# ASD2116.net
KiCad netlist of a schematic drawn in EAGLE
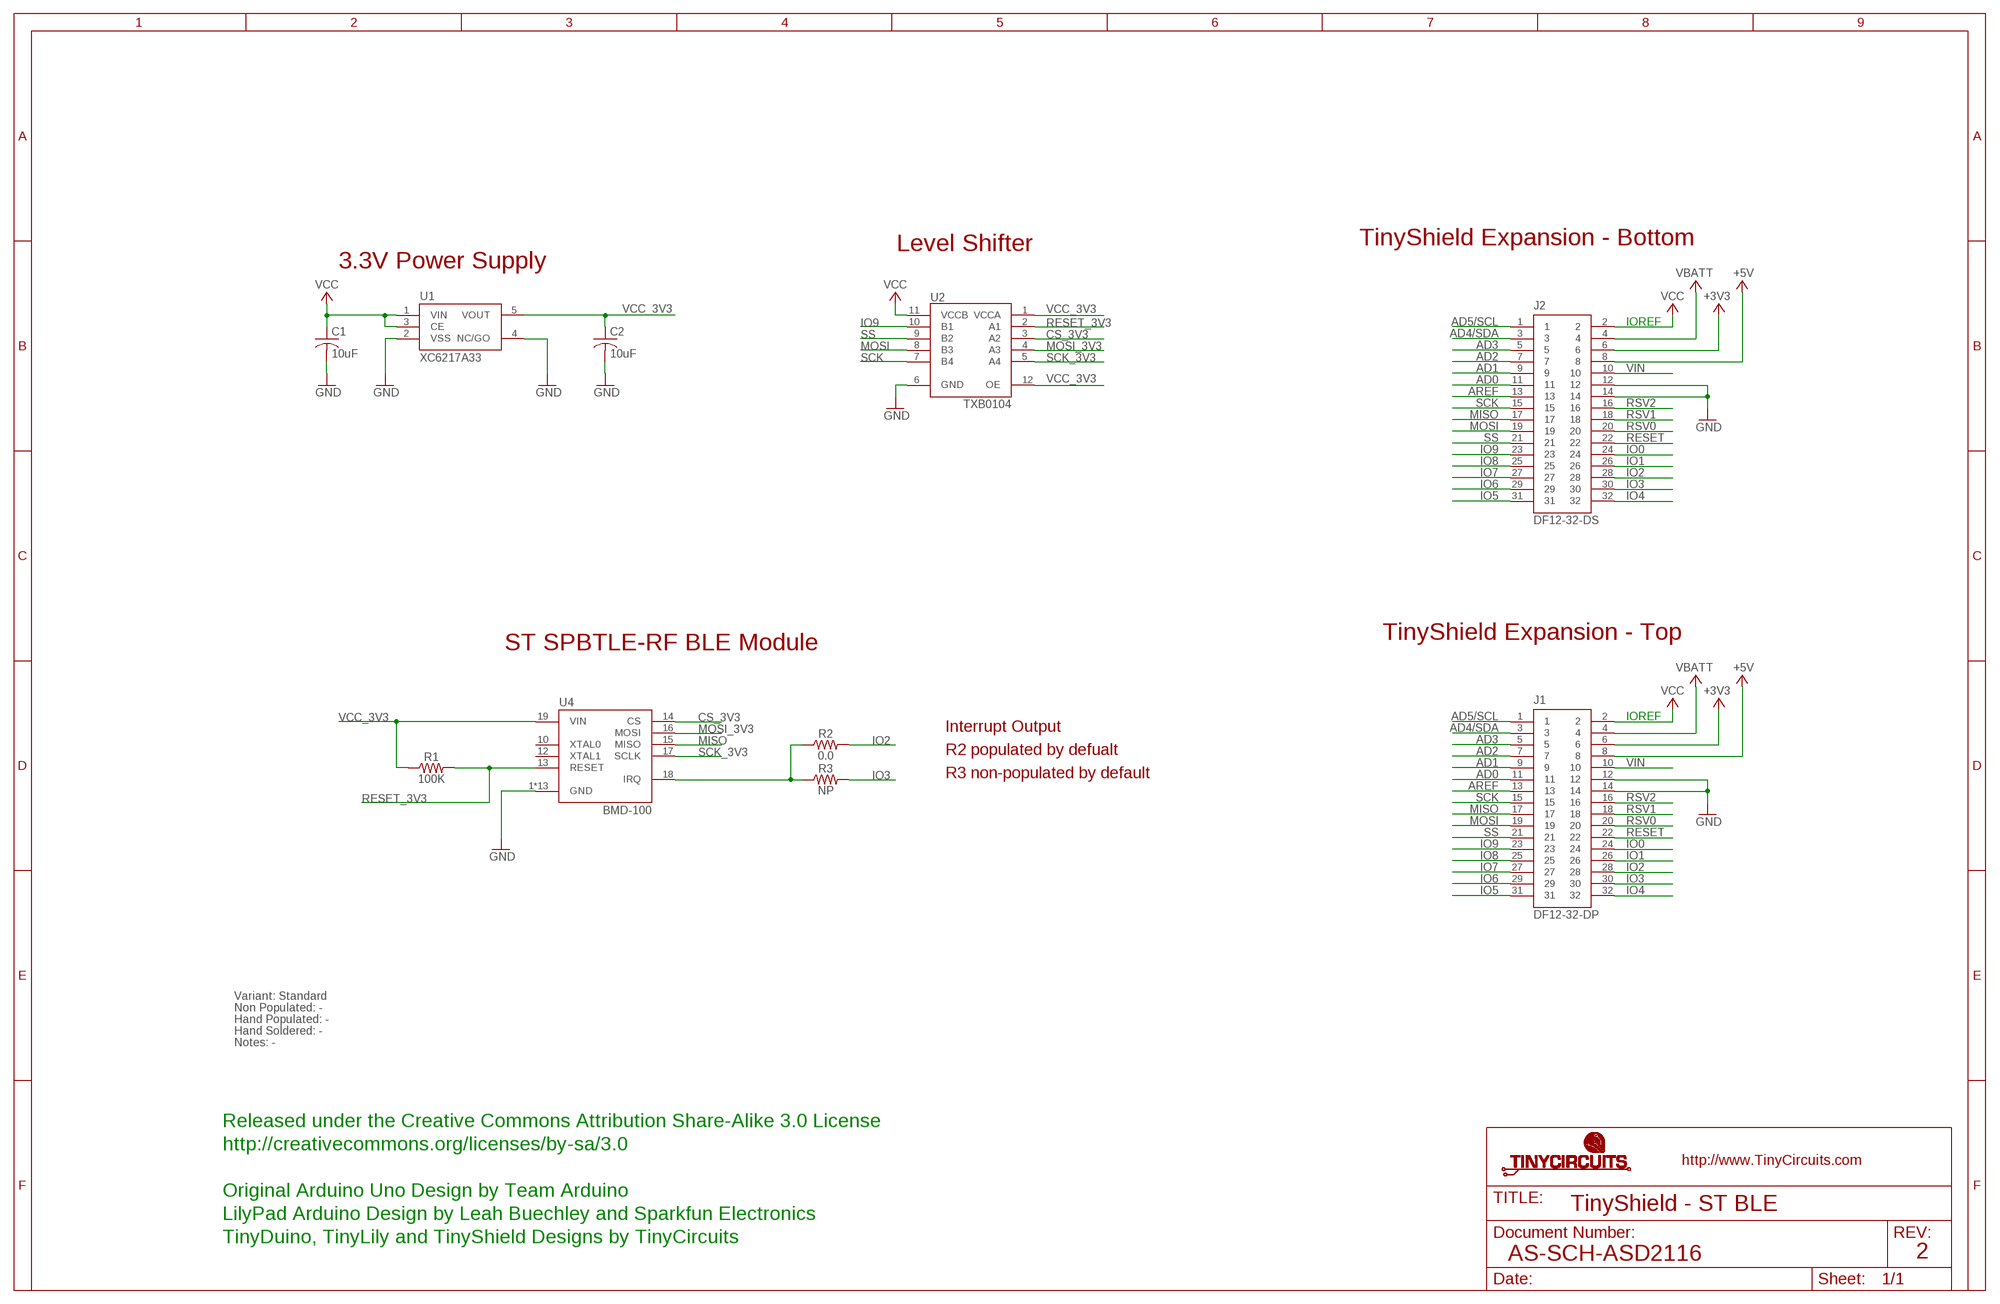
[diagram p0: schematic, sheet 1]

(export (version "E")
  (design (tool "Eeschema 10.0.6"))
  (components
    (comp (ref "C1")
      (value "10uF")
      (footprint "eagle-import:C0603")
      (fields (field (name "PARTNO") "AS-ITM-00002") (field (name "PARTNO_1") "AS-ITM-00002"))
      (libsource (lib "eagle-import") (part "AS-ITM-00002"))
    )
    (comp (ref "C2")
      (value "10uF")
      (footprint "eagle-import:C0603")
      (fields (field (name "PARTNO") "AS-ITM-00002") (field (name "PARTNO_1") "AS-ITM-00002"))
      (libsource (lib "eagle-import") (part "AS-ITM-00002"))
    )
    (comp (ref "J1")
      (value "DF12-32-DP")
      (footprint "eagle-import:DF12-32-DP")
      (fields (field (name "PARTNO") "AS-ITM-00015") (field (name "PARTNO_1") "AS-ITM-00015"))
      (libsource (lib "eagle-import") (part "AS-ITM-00015"))
    )
    (comp (ref "J2")
      (value "DF12-32-DS")
      (footprint "eagle-import:DF12-32-DS")
      (fields (field (name "PARTNO") "AS-ITM-00012") (field (name "PARTNO_1") "AS-ITM-00012"))
      (libsource (lib "eagle-import") (part "AS-ITM-00012"))
    )
    (comp (ref "R1")
      (value "100K")
      (footprint "eagle-import:0402")
      (fields (field (name "PARTNO") "AS-ITM-00004"))
      (libsource (lib "eagle-import") (part "AS-ITM-00004"))
    )
    (comp (ref "R2")
      (value "0.0")
      (footprint "eagle-import:0402")
      (fields (field (name "PARTNO") "AS-ITM-00076") (field (name "PARTNO_1") "AS-ITM-00076"))
      (libsource (lib "eagle-import") (part "AS-ITM-00076"))
    )
    (comp (ref "R3")
      (value "NP")
      (footprint "eagle-import:0402")
      (fields (field (name "PARTNO") "AS-ITM-00076") (field (name "PARTNO_1") "AS-ITM-00076"))
      (libsource (lib "eagle-import") (part "AS-ITM-00076"))
    )
    (comp (ref "U1")
      (value "XC6217A33")
      (footprint "eagle-import:SOT-25")
      (fields (field (name "PARTNO") "AS-ITM-00249") (field (name "PARTNO_1") "AS-ITM-00249"))
      (libsource (lib "eagle-import") (part "AS-ITM-00249"))
    )
    (comp (ref "U2")
      (value "TXB0104")
      (footprint "eagle-import:UQFN-12")
      (fields (field (name "PARTNO") "AS-ITM-00048"))
      (libsource (lib "eagle-import") (part "AS-ITM-00048"))
    )
    (comp (ref "U4")
      (value "BMD-100")
      (footprint "eagle-import:BMD-100")
      (fields (field (name "PARTNO") "AS-ITM-00402"))
      (libsource (lib "eagle-import") (part "AS-ITM-00402"))
    )
  )
  (nets
    (net (code "1") (name "+3V3") (class "Default")
      (node (ref "J1") (pin "6") (pinfunction "6_6") (pintype "bidirectional"))
      (node (ref "J2") (pin "6") (pinfunction "6_6") (pintype "bidirectional"))
    )
    (net (code "2") (name "+5V") (class "Default")
      (node (ref "J1") (pin "8") (pinfunction "8_8") (pintype "bidirectional"))
      (node (ref "J2") (pin "8") (pinfunction "8_8") (pintype "bidirectional"))
    )
    (net (code "3") (name "/AD0") (class "Default")
      (node (ref "J1") (pin "11") (pinfunction "11_11") (pintype "bidirectional"))
      (node (ref "J2") (pin "11") (pinfunction "11_11") (pintype "bidirectional"))
    )
    (net (code "4") (name "/AD1") (class "Default")
      (node (ref "J1") (pin "9") (pinfunction "9_9") (pintype "bidirectional"))
      (node (ref "J2") (pin "9") (pinfunction "9_9") (pintype "bidirectional"))
    )
    (net (code "5") (name "/AD2") (class "Default")
      (node (ref "J1") (pin "7") (pinfunction "7_7") (pintype "bidirectional"))
      (node (ref "J2") (pin "7") (pinfunction "7_7") (pintype "bidirectional"))
    )
    (net (code "6") (name "/AD3") (class "Default")
      (node (ref "J1") (pin "5") (pinfunction "5_5") (pintype "bidirectional"))
      (node (ref "J2") (pin "5") (pinfunction "5_5") (pintype "bidirectional"))
    )
    (net (code "7") (name "/AD4{slash}SDA") (class "Default")
      (node (ref "J1") (pin "3") (pinfunction "3_3") (pintype "bidirectional"))
      (node (ref "J2") (pin "3") (pinfunction "3_3") (pintype "bidirectional"))
    )
    (net (code "8") (name "/AD5{slash}SCL") (class "Default")
      (node (ref "J1") (pin "1") (pinfunction "1_1") (pintype "bidirectional"))
      (node (ref "J2") (pin "1") (pinfunction "1_1") (pintype "bidirectional"))
    )
    (net (code "9") (name "/AREF") (class "Default")
      (node (ref "J1") (pin "13") (pinfunction "13_13") (pintype "bidirectional"))
      (node (ref "J2") (pin "13") (pinfunction "13_13") (pintype "bidirectional"))
    )
    (net (code "10") (name "/CS_3V3") (class "Default")
      (node (ref "U2") (pin "3") (pinfunction "A2_3") (pintype "bidirectional"))
      (node (ref "U4") (pin "14") (pinfunction "CS_14") (pintype "bidirectional"))
    )
    (net (code "11") (name "/IO0") (class "Default")
      (node (ref "J1") (pin "24") (pinfunction "24_24") (pintype "bidirectional"))
      (node (ref "J2") (pin "24") (pinfunction "24_24") (pintype "bidirectional"))
    )
    (net (code "12") (name "/IO1") (class "Default")
      (node (ref "J1") (pin "26") (pinfunction "26_26") (pintype "bidirectional"))
      (node (ref "J2") (pin "26") (pinfunction "26_26") (pintype "bidirectional"))
    )
    (net (code "13") (name "/IO2") (class "Default")
      (node (ref "J1") (pin "28") (pinfunction "28_28") (pintype "bidirectional"))
      (node (ref "J2") (pin "28") (pinfunction "28_28") (pintype "bidirectional"))
      (node (ref "R2") (pin "2") (pinfunction "2_2") (pintype "passive"))
    )
    (net (code "14") (name "/IO3") (class "Default")
      (node (ref "J1") (pin "30") (pinfunction "30_30") (pintype "bidirectional"))
      (node (ref "J2") (pin "30") (pinfunction "30_30") (pintype "bidirectional"))
      (node (ref "R3") (pin "2") (pinfunction "2_2") (pintype "passive"))
    )
    (net (code "15") (name "/IO4") (class "Default")
      (node (ref "J1") (pin "32") (pinfunction "32_32") (pintype "bidirectional"))
      (node (ref "J2") (pin "32") (pinfunction "32_32") (pintype "bidirectional"))
    )
    (net (code "16") (name "/IO5") (class "Default")
      (node (ref "J1") (pin "31") (pinfunction "31_31") (pintype "bidirectional"))
      (node (ref "J2") (pin "31") (pinfunction "31_31") (pintype "bidirectional"))
    )
    (net (code "17") (name "/IO6") (class "Default")
      (node (ref "J1") (pin "29") (pinfunction "29_29") (pintype "bidirectional"))
      (node (ref "J2") (pin "29") (pinfunction "29_29") (pintype "bidirectional"))
    )
    (net (code "18") (name "/IO7") (class "Default")
      (node (ref "J1") (pin "27") (pinfunction "27_27") (pintype "bidirectional"))
      (node (ref "J2") (pin "27") (pinfunction "27_27") (pintype "bidirectional"))
    )
    (net (code "19") (name "/IO8") (class "Default")
      (node (ref "J1") (pin "25") (pinfunction "25_25") (pintype "bidirectional"))
      (node (ref "J2") (pin "25") (pinfunction "25_25") (pintype "bidirectional"))
    )
    (net (code "20") (name "/IO9") (class "Default")
      (node (ref "J1") (pin "23") (pinfunction "23_23") (pintype "bidirectional"))
      (node (ref "J2") (pin "23") (pinfunction "23_23") (pintype "bidirectional"))
      (node (ref "U2") (pin "10") (pinfunction "B1_10") (pintype "bidirectional"))
    )
    (net (code "21") (name "/MISO") (class "Default")
      (node (ref "J1") (pin "17") (pinfunction "17_17") (pintype "bidirectional"))
      (node (ref "J2") (pin "17") (pinfunction "17_17") (pintype "bidirectional"))
      (node (ref "U4") (pin "15") (pinfunction "MISO_15") (pintype "bidirectional"))
    )
    (net (code "22") (name "/MOSI") (class "Default")
      (node (ref "J1") (pin "19") (pinfunction "19_19") (pintype "bidirectional"))
      (node (ref "J2") (pin "19") (pinfunction "19_19") (pintype "bidirectional"))
      (node (ref "U2") (pin "8") (pinfunction "B3_8") (pintype "bidirectional"))
    )
    (net (code "23") (name "/MOSI_3V3") (class "Default")
      (node (ref "U2") (pin "4") (pinfunction "A3_4") (pintype "bidirectional"))
      (node (ref "U4") (pin "16") (pinfunction "MOSI_16") (pintype "bidirectional"))
    )
    (net (code "24") (name "/RESET") (class "Default")
      (node (ref "J1") (pin "22") (pinfunction "22_22") (pintype "bidirectional"))
      (node (ref "J2") (pin "22") (pinfunction "22_22") (pintype "bidirectional"))
    )
    (net (code "25") (name "/RESET_3V3") (class "Default")
      (node (ref "R1") (pin "2") (pinfunction "2_2") (pintype "passive"))
      (node (ref "U2") (pin "2") (pinfunction "A1_2") (pintype "bidirectional"))
      (node (ref "U4") (pin "13") (pinfunction "RESET_13") (pintype "bidirectional"))
    )
    (net (code "26") (name "/RSV0") (class "Default")
      (node (ref "J1") (pin "20") (pinfunction "20_20") (pintype "bidirectional"))
      (node (ref "J2") (pin "20") (pinfunction "20_20") (pintype "bidirectional"))
    )
    (net (code "27") (name "/RSV1") (class "Default")
      (node (ref "J1") (pin "18") (pinfunction "18_18") (pintype "bidirectional"))
      (node (ref "J2") (pin "18") (pinfunction "18_18") (pintype "bidirectional"))
    )
    (net (code "28") (name "/RSV2") (class "Default")
      (node (ref "J1") (pin "16") (pinfunction "16_16") (pintype "bidirectional"))
      (node (ref "J2") (pin "16") (pinfunction "16_16") (pintype "bidirectional"))
    )
    (net (code "29") (name "/SCK") (class "Default")
      (node (ref "J1") (pin "15") (pinfunction "15_15") (pintype "bidirectional"))
      (node (ref "J2") (pin "15") (pinfunction "15_15") (pintype "bidirectional"))
      (node (ref "U2") (pin "7") (pinfunction "B4_7") (pintype "bidirectional"))
    )
    (net (code "30") (name "/SCK_3V3") (class "Default")
      (node (ref "U2") (pin "5") (pinfunction "A4_5") (pintype "bidirectional"))
      (node (ref "U4") (pin "17") (pinfunction "SCLK_17") (pintype "bidirectional"))
    )
    (net (code "31") (name "/SS") (class "Default")
      (node (ref "J1") (pin "21") (pinfunction "21_21") (pintype "bidirectional"))
      (node (ref "J2") (pin "21") (pinfunction "21_21") (pintype "bidirectional"))
      (node (ref "U2") (pin "9") (pinfunction "B2_9") (pintype "bidirectional"))
    )
    (net (code "32") (name "/VCC_3V3") (class "Default")
      (node (ref "C2") (pin "1") (pinfunction "1_1") (pintype "passive"))
      (node (ref "R1") (pin "1") (pinfunction "1_1") (pintype "passive"))
      (node (ref "U1") (pin "5") (pinfunction "VOUT_5") (pintype "bidirectional"))
      (node (ref "U2") (pin "1") (pinfunction "VCCA_1") (pintype "bidirectional"))
      (node (ref "U2") (pin "12") (pinfunction "OE_12") (pintype "bidirectional"))
      (node (ref "U4") (pin "19") (pinfunction "VIN_19") (pintype "bidirectional"))
    )
    (net (code "33") (name "/VIN") (class "Default")
      (node (ref "J1") (pin "10") (pinfunction "10_10") (pintype "bidirectional"))
      (node (ref "J2") (pin "10") (pinfunction "10_10") (pintype "bidirectional"))
    )
    (net (code "34") (name "GND") (class "Default")
      (node (ref "C1") (pin "2") (pinfunction "2_2") (pintype "passive"))
      (node (ref "C2") (pin "2") (pinfunction "2_2") (pintype "passive"))
      (node (ref "J1") (pin "12") (pinfunction "12_12") (pintype "bidirectional"))
      (node (ref "J1") (pin "14") (pinfunction "14_14") (pintype "bidirectional"))
      (node (ref "J2") (pin "12") (pinfunction "12_12") (pintype "bidirectional"))
      (node (ref "J2") (pin "14") (pinfunction "14_14") (pintype "bidirectional"))
      (node (ref "U1") (pin "2") (pinfunction "VSS_2") (pintype "power_in"))
      (node (ref "U1") (pin "4") (pinfunction "NC/GO_4") (pintype "bidirectional"))
      (node (ref "U2") (pin "6") (pinfunction "GND_6") (pintype "bidirectional"))
      (node (ref "U4") (pin "1") (pinfunction "GND_1") (pintype "bidirectional"))
      (node (ref "U4") (pin "11") (pinfunction "GND_11") (pintype "bidirectional"))
      (node (ref "U4") (pin "2") (pinfunction "GND_2") (pintype "bidirectional"))
      (node (ref "U4") (pin "20") (pinfunction "GND_20") (pintype "bidirectional"))
      (node (ref "U4") (pin "3") (pinfunction "GND_3") (pintype "bidirectional"))
      (node (ref "U4") (pin "7") (pinfunction "GND_7") (pintype "bidirectional"))
      (node (ref "U4") (pin "9") (pinfunction "GND_9") (pintype "bidirectional"))
      (node (ref "U4") (pin "A") (pinfunction "GND_A") (pintype "bidirectional"))
      (node (ref "U4") (pin "B") (pinfunction "GND_B") (pintype "bidirectional"))
      (node (ref "U4") (pin "C") (pinfunction "GND_C") (pintype "bidirectional"))
      (node (ref "U4") (pin "D") (pinfunction "GND_D") (pintype "bidirectional"))
      (node (ref "U4") (pin "E") (pinfunction "GND_E") (pintype "bidirectional"))
      (node (ref "U4") (pin "F") (pinfunction "GND_F") (pintype "bidirectional"))
    )
    (net (code "35") (name "Net-(U4-IRQ)") (class "Default")
      (node (ref "R2") (pin "1") (pinfunction "1_1") (pintype "passive"))
      (node (ref "R3") (pin "1") (pinfunction "1_1") (pintype "passive"))
      (node (ref "U4") (pin "18") (pinfunction "IRQ_18") (pintype "bidirectional"))
    )
    (net (code "36") (name "VBATT") (class "Default")
      (node (ref "J1") (pin "4") (pinfunction "4_4") (pintype "bidirectional"))
      (node (ref "J2") (pin "4") (pinfunction "4_4") (pintype "bidirectional"))
    )
    (net (code "37") (name "VCC") (class "Default")
      (node (ref "C1") (pin "1") (pinfunction "1_1") (pintype "passive"))
      (node (ref "J1") (pin "2") (pinfunction "2_2") (pintype "bidirectional"))
      (node (ref "J2") (pin "2") (pinfunction "2_2") (pintype "bidirectional"))
      (node (ref "U1") (pin "1") (pinfunction "VIN_1") (pintype "bidirectional"))
      (node (ref "U1") (pin "3") (pinfunction "CE_3") (pintype "bidirectional"))
      (node (ref "U2") (pin "11") (pinfunction "VCCB_11") (pintype "bidirectional"))
    )
    (net (code "38") (name "unconnected-(U4-XTAL0-Pad10)") (class "Default")
      (node (ref "U4") (pin "10") (pinfunction "XTAL0_10") (pintype "bidirectional"))
    )
    (net (code "39") (name "unconnected-(U4-XTAL1-Pad12)") (class "Default")
      (node (ref "U4") (pin "12") (pinfunction "XTAL1_12") (pintype "bidirectional"))
    )
  )
)
